# AM32_ESC.net
KiCad netlist of a schematic drawn in Altium Designer
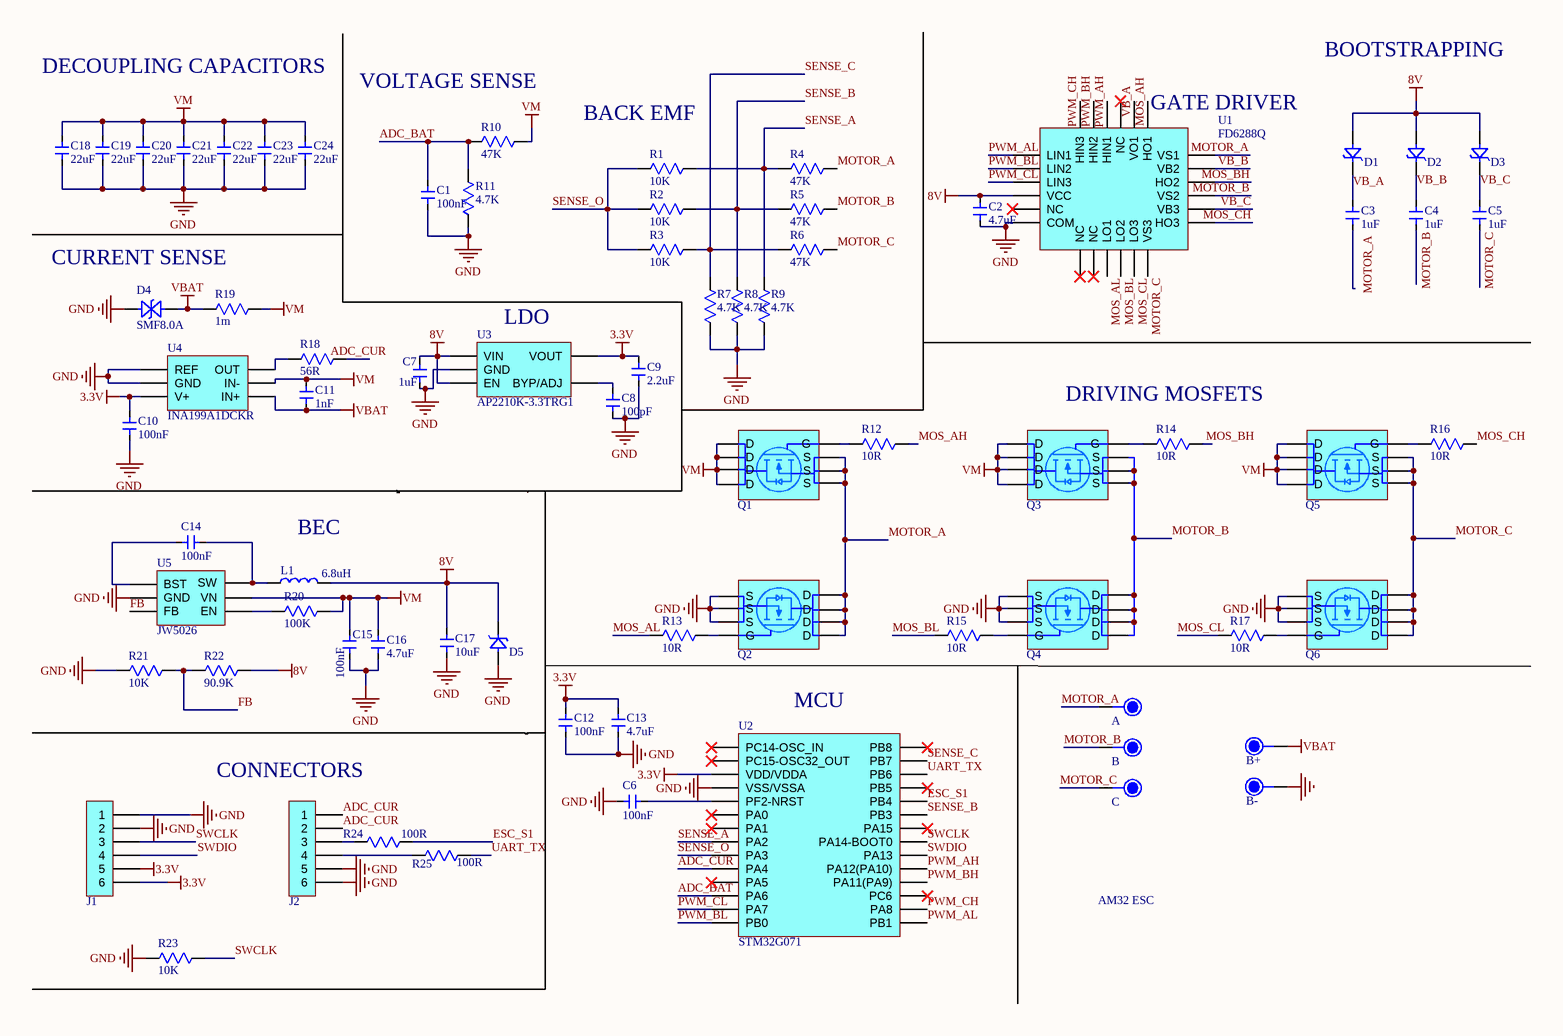
[diagram p0: AM32_ESC.SchDoc]

(export (version "E")
  (design (tool "Eeschema 10.0.6"))
  (components
    (comp (ref "A") (value "PAD") (footprint "PAD") (libsource (lib "AM32_ESC") (part "PAD")))
    (comp (ref "B") (value "PAD") (footprint "PAD") (libsource (lib "AM32_ESC") (part "PAD")))
    (comp (ref "B+") (value "PAD") (footprint "PAD") (libsource (lib "AM32_ESC") (part "PAD")))
    (comp (ref "B-") (value "PAD") (footprint "PAD") (libsource (lib "AM32_ESC") (part "PAD")))
    (comp (ref "C") (value "PAD") (footprint "PAD") (libsource (lib "AM32_ESC") (part "PAD")))
    (comp (ref "C1") (value "100nF") (footprint "C0805") (libsource (lib "AM32_ESC") (part "C100nF")))
    (comp (ref "C2") (value "4.7uF") (footprint "C0603") (libsource (lib "AM32_ESC") (part "C4.7uF")))
    (comp (ref "C3") (value "1uF") (footprint "C0603") (libsource (lib "AM32_ESC") (part "C1uF")))
    (comp (ref "C4") (value "1uF") (footprint "C0603") (libsource (lib "AM32_ESC") (part "C1uF")))
    (comp (ref "C5") (value "1uF") (footprint "C0603") (libsource (lib "AM32_ESC") (part "C1uF")))
    (comp (ref "C6") (value "100nF") (footprint "C0805") (libsource (lib "AM32_ESC") (part "C100nF")))
    (comp (ref "C7") (value "1uF") (footprint "C0603") (libsource (lib "AM32_ESC") (part "C1uF")))
    (comp (ref "C8") (value "100pF") (footprint "C0603") (libsource (lib "AM32_ESC") (part "C100pF")))
    (comp (ref "C9") (value "2.2uF") (footprint "C0603") (libsource (lib "AM32_ESC") (part "C2.2uF")))
    (comp (ref "C10") (value "100nF") (footprint "C0805") (libsource (lib "AM32_ESC") (part "C100nF")))
    (comp (ref "C11") (value "1nF") (footprint "C0603") (libsource (lib "AM32_ESC") (part "C1nF")))
    (comp (ref "C12") (value "100nF") (footprint "C0805") (libsource (lib "AM32_ESC") (part "C100nF")))
    (comp (ref "C13") (value "4.7uF") (footprint "C0603") (libsource (lib "AM32_ESC") (part "C4.7uF")))
    (comp (ref "C14") (value "100nF") (footprint "C0805") (libsource (lib "AM32_ESC") (part "C100nF")))
    (comp (ref "C15") (value "100nF") (footprint "C0805") (libsource (lib "AM32_ESC") (part "C100nF")))
    (comp (ref "C16") (value "4.7uF") (footprint "C0603") (libsource (lib "AM32_ESC") (part "C4.7uF")))
    (comp (ref "C17") (value "10uF") (footprint "C0603") (libsource (lib "AM32_ESC") (part "C10uF")))
    (comp (ref "C18") (value "22uF") (footprint "C0805") (libsource (lib "AM32_ESC") (part "C22uF")))
    (comp (ref "C19") (value "22uF") (footprint "C0805") (libsource (lib "AM32_ESC") (part "C22uF")))
    (comp (ref "C20") (value "22uF") (footprint "C0805") (libsource (lib "AM32_ESC") (part "C22uF")))
    (comp (ref "C21") (value "22uF") (footprint "C0805") (libsource (lib "AM32_ESC") (part "C22uF")))
    (comp (ref "C22") (value "22uF") (footprint "C0805") (libsource (lib "AM32_ESC") (part "C22uF")))
    (comp (ref "C23") (value "22uF") (footprint "C0805") (libsource (lib "AM32_ESC") (part "C22uF")))
    (comp (ref "C24") (value "22uF") (footprint "C0805") (libsource (lib "AM32_ESC") (part "C22uF")))
    (comp (ref "D1") (value "Diode") (footprint "SOD2512X116N") (libsource (lib "AM32_ESC") (part "Diode")))
    (comp (ref "D2") (value "Diode") (footprint "SOD2512X116N") (libsource (lib "AM32_ESC") (part "Diode")))
    (comp (ref "D3") (value "Diode") (footprint "SOD2512X116N") (libsource (lib "AM32_ESC") (part "Diode")))
    (comp (ref "D4") (value "SMF8.0A") (footprint "SMF8.0") (libsource (lib "AM32_ESC") (part "SMF8.0A")))
    (comp (ref "D5") (value "Diode") (footprint "SOD2512X116N") (libsource (lib "AM32_ESC") (part "Diode")))
    (comp (ref "J1") (value "JST_XH") (footprint "6 pin header") (libsource (lib "AM32_ESC") (part "JST_XH")))
    (comp (ref "J2") (value "JST_XH") (footprint "6 pin header") (libsource (lib "AM32_ESC") (part "JST_XH")))
    (comp (ref "L1") (value "6.8uH") (footprint "L0806") (libsource (lib "AM32_ESC") (part "L6.8uH")))
    (comp (ref "Q1")
      (value "CSD19531")
      (footprint "MOSFET_CSD19531Q5A")
      (libsource (lib "") (part "MOSFET_1"))
    )
    (comp (ref "Q2")
      (value "CSD19531")
      (footprint "MOSFET_CSD19531Q5A")
      (libsource (lib "AM32_ESC") (part "MOSFET"))
    )
    (comp (ref "Q3")
      (value "CSD19531")
      (footprint "MOSFET_CSD19531Q5A")
      (libsource (lib "") (part "MOSFET_1"))
    )
    (comp (ref "Q4")
      (value "CSD19531")
      (footprint "MOSFET_CSD19531Q5A")
      (libsource (lib "AM32_ESC") (part "MOSFET"))
    )
    (comp (ref "Q5")
      (value "CSD19531")
      (footprint "MOSFET_CSD19531Q5A")
      (libsource (lib "") (part "MOSFET_1"))
    )
    (comp (ref "Q6")
      (value "CSD19531")
      (footprint "MOSFET_CSD19531Q5A")
      (libsource (lib "AM32_ESC") (part "MOSFET"))
    )
    (comp (ref "R1") (value "10K") (footprint "R0603n") (libsource (lib "AM32_ESC") (part "R10K")))
    (comp (ref "R2") (value "10K") (footprint "R0603n") (libsource (lib "AM32_ESC") (part "R10K")))
    (comp (ref "R3") (value "10K") (footprint "R0603n") (libsource (lib "AM32_ESC") (part "R10K")))
    (comp (ref "R4") (value "47K") (footprint "R0603N") (libsource (lib "AM32_ESC") (part "R47K")))
    (comp (ref "R5") (value "47K") (footprint "R0603N") (libsource (lib "AM32_ESC") (part "R47K")))
    (comp (ref "R6") (value "47K") (footprint "R0603N") (libsource (lib "AM32_ESC") (part "R47K")))
    (comp (ref "R7") (value "4.7K") (footprint "R0603N") (libsource (lib "AM32_ESC") (part "R4.7K")))
    (comp (ref "R8") (value "4.7K") (footprint "R0603N") (libsource (lib "AM32_ESC") (part "R4.7K")))
    (comp (ref "R9") (value "4.7K") (footprint "R0603N") (libsource (lib "AM32_ESC") (part "R4.7K")))
    (comp (ref "R10") (value "47K") (footprint "R0603N") (libsource (lib "AM32_ESC") (part "R47K")))
    (comp (ref "R11") (value "4.7K") (footprint "R0603N") (libsource (lib "AM32_ESC") (part "R4.7K")))
    (comp (ref "R12") (value "10R") (footprint "R0603n") (libsource (lib "AM32_ESC") (part "R10")))
    (comp (ref "R13") (value "10R") (footprint "R0603n") (libsource (lib "AM32_ESC") (part "R10")))
    (comp (ref "R14") (value "10R") (footprint "R0603n") (libsource (lib "AM32_ESC") (part "R10")))
    (comp (ref "R15") (value "10R") (footprint "R0603n") (libsource (lib "AM32_ESC") (part "R10")))
    (comp (ref "R16") (value "10R") (footprint "R0603n") (libsource (lib "AM32_ESC") (part "R10")))
    (comp (ref "R17") (value "10R") (footprint "R0603n") (libsource (lib "AM32_ESC") (part "R10")))
    (comp (ref "R18") (value "56R") (footprint "R0603N") (libsource (lib "AM32_ESC") (part "R56")))
    (comp (ref "R19") (value "1m") (footprint "RESC5025X120N") (libsource (lib "AM32_ESC") (part "R1m")))
    (comp (ref "R20") (value "100K") (footprint "R0603N") (libsource (lib "AM32_ESC") (part "R100K")))
    (comp (ref "R21") (value "10K") (footprint "R0603n") (libsource (lib "AM32_ESC") (part "R10K")))
    (comp (ref "R22") (value "90.9K") (footprint "R0603N") (libsource (lib "AM32_ESC") (part "R90.9k")))
    (comp (ref "R23") (value "10K") (footprint "R0603n") (libsource (lib "AM32_ESC") (part "R10K")))
    (comp (ref "R24") (value "100R") (footprint "R0603") (libsource (lib "AM32_ESC") (part "100R")))
    (comp (ref "R25") (value "100R") (footprint "R0603") (libsource (lib "AM32_ESC") (part "100R")))
    (comp (ref "U1") (value "FD6288Q") (footprint "FD6288Q") (libsource (lib "AM32_ESC") (part "FD6288Q")))
    (comp (ref "U2")
      (value "STM32G071")
      (footprint "STM32G071")
      (libsource (lib "AM32_ESC") (part "STM32G071"))
    )
    (comp (ref "U3")
      (value "AP2210K-3.3TRG1")
      (footprint "AP2210K-3.3TRG1")
      (libsource (lib "AM32_ESC") (part "AP2210K-3.3TRG1"))
    )
    (comp (ref "U4")
      (value "INA199A1DCKR")
      (footprint "INA199A1DCKR")
      (libsource (lib "AM32_ESC") (part "INA199A1DCKR"))
    )
    (comp (ref "U5") (value "JW5026") (footprint "JW5026") (libsource (lib "AM32_ESC") (part "JW5026")))
  )
  (nets
    (net (code "1") (name "/ADC_BAT") (class "Default")
      (node (ref "C1") (pin "2") (pinfunction "2_2") (pintype "passive"))
      (node (ref "R10") (pin "1") (pinfunction "1_1") (pintype "passive"))
      (node (ref "R11") (pin "2") (pinfunction "2_2") (pintype "passive"))
      (node (ref "U2") (pin "12") (pinfunction "PA6_12") (pintype "passive"))
    )
    (net (code "2") (name "/ADC_CUR") (class "Default")
      (node (ref "J2") (pin "1") (pinfunction "1_1") (pintype "passive"))
      (node (ref "J2") (pin "2") (pinfunction "2_2") (pintype "passive"))
      (node (ref "R18") (pin "2") (pinfunction "2_2") (pintype "passive"))
      (node (ref "U2") (pin "10") (pinfunction "PA4_10") (pintype "passive"))
    )
    (net (code "3") (name "/ESC_S1") (class "Default")
      (node (ref "R24") (pin "2") (pinfunction "2_2") (pintype "passive"))
      (node (ref "U2") (pin "24") (pinfunction "PB4_24") (pintype "passive"))
    )
    (net (code "4") (name "/FB") (class "Default")
      (node (ref "R21") (pin "2") (pinfunction "2_2") (pintype "passive"))
      (node (ref "R22") (pin "1") (pinfunction "1_1") (pintype "passive"))
      (node (ref "U5") (pin "3") (pinfunction "FB_3") (pintype "passive"))
    )
    (net (code "5") (name "/MOS_AH") (class "Default")
      (node (ref "R12") (pin "2") (pinfunction "2_2") (pintype "passive"))
      (node (ref "U1") (pin "19") (pinfunction "HO1_19") (pintype "passive"))
    )
    (net (code "6") (name "/MOS_AL") (class "Default")
      (node (ref "R13") (pin "1") (pinfunction "1_1") (pintype "passive"))
      (node (ref "U1") (pin "9") (pinfunction "LO1_9") (pintype "passive"))
    )
    (net (code "7") (name "/MOS_BH") (class "Default")
      (node (ref "R14") (pin "2") (pinfunction "2_2") (pintype "passive"))
      (node (ref "U1") (pin "16") (pinfunction "HO2_16") (pintype "passive"))
    )
    (net (code "8") (name "/MOS_BL") (class "Default")
      (node (ref "R15") (pin "1") (pinfunction "1_1") (pintype "passive"))
      (node (ref "U1") (pin "10") (pinfunction "LO2_10") (pintype "passive"))
    )
    (net (code "9") (name "/MOS_CH") (class "Default")
      (node (ref "R16") (pin "2") (pinfunction "2_2") (pintype "passive"))
      (node (ref "U1") (pin "13") (pinfunction "HO3_13") (pintype "passive"))
    )
    (net (code "10") (name "/MOS_CL") (class "Default")
      (node (ref "R17") (pin "1") (pinfunction "1_1") (pintype "passive"))
      (node (ref "U1") (pin "11") (pinfunction "LO3_11") (pintype "passive"))
    )
    (net (code "11") (name "/MOTOR_A") (class "Default")
      (node (ref "A") (pin "1") (pinfunction "1_1") (pintype "passive"))
      (node (ref "Q1") (pin "1") (pinfunction "S_1") (pintype "passive"))
      (node (ref "Q1") (pin "2") (pinfunction "S_2") (pintype "passive"))
      (node (ref "Q1") (pin "3") (pinfunction "S_3") (pintype "passive"))
      (node (ref "Q2") (pin "5") (pinfunction "D_5") (pintype "passive"))
      (node (ref "Q2") (pin "6") (pinfunction "D_6") (pintype "passive"))
      (node (ref "Q2") (pin "7") (pinfunction "D_7") (pintype "passive"))
      (node (ref "Q2") (pin "8") (pinfunction "D_8") (pintype "passive"))
      (node (ref "R4") (pin "2") (pinfunction "2_2") (pintype "passive"))
      (node (ref "U1") (pin "18") (pinfunction "VS1_18") (pintype "passive"))
    )
    (net (code "12") (name "/MOTOR_B") (class "Default")
      (node (ref "B") (pin "1") (pinfunction "1_1") (pintype "passive"))
      (node (ref "Q3") (pin "1") (pinfunction "S_1") (pintype "passive"))
      (node (ref "Q3") (pin "2") (pinfunction "S_2") (pintype "passive"))
      (node (ref "Q3") (pin "3") (pinfunction "S_3") (pintype "passive"))
      (node (ref "Q4") (pin "5") (pinfunction "D_5") (pintype "passive"))
      (node (ref "Q4") (pin "6") (pinfunction "D_6") (pintype "passive"))
      (node (ref "Q4") (pin "7") (pinfunction "D_7") (pintype "passive"))
      (node (ref "Q4") (pin "8") (pinfunction "D_8") (pintype "passive"))
      (node (ref "R5") (pin "2") (pinfunction "2_2") (pintype "passive"))
      (node (ref "U1") (pin "15") (pinfunction "VS2_15") (pintype "passive"))
    )
    (net (code "13") (name "/MOTOR_C") (class "Default")
      (node (ref "C") (pin "1") (pinfunction "1_1") (pintype "passive"))
      (node (ref "Q5") (pin "1") (pinfunction "S_1") (pintype "passive"))
      (node (ref "Q5") (pin "2") (pinfunction "S_2") (pintype "passive"))
      (node (ref "Q5") (pin "3") (pinfunction "S_3") (pintype "passive"))
      (node (ref "Q6") (pin "5") (pinfunction "D_5") (pintype "passive"))
      (node (ref "Q6") (pin "6") (pinfunction "D_6") (pintype "passive"))
      (node (ref "Q6") (pin "7") (pinfunction "D_7") (pintype "passive"))
      (node (ref "Q6") (pin "8") (pinfunction "D_8") (pintype "passive"))
      (node (ref "R6") (pin "2") (pinfunction "2_2") (pintype "passive"))
      (node (ref "U1") (pin "12") (pinfunction "VS3_12") (pintype "passive"))
    )
    (net (code "14") (name "/PWM_AH") (class "Default")
      (node (ref "U1") (pin "22") (pinfunction "HIN1_22") (pintype "passive"))
      (node (ref "U2") (pin "19") (pinfunction "PA12(PA10)_19") (pintype "passive"))
    )
    (net (code "15") (name "/PWM_AL") (class "Default")
      (node (ref "U1") (pin "1") (pinfunction "LIN1_1") (pintype "passive"))
      (node (ref "U2") (pin "15") (pinfunction "PB1_15") (pintype "passive"))
    )
    (net (code "16") (name "/PWM_BH") (class "Default")
      (node (ref "U1") (pin "23") (pinfunction "HIN2_23") (pintype "passive"))
      (node (ref "U2") (pin "18") (pinfunction "PA11(PA9)_18") (pintype "passive"))
    )
    (net (code "17") (name "/PWM_BL") (class "Default")
      (node (ref "U1") (pin "2") (pinfunction "LIN2_2") (pintype "passive"))
      (node (ref "U2") (pin "14") (pinfunction "PB0_14") (pintype "passive"))
    )
    (net (code "18") (name "/PWM_CH") (class "Default")
      (node (ref "U1") (pin "24") (pinfunction "HIN3_24") (pintype "passive"))
      (node (ref "U2") (pin "16") (pinfunction "PA8_16") (pintype "passive"))
    )
    (net (code "19") (name "/PWM_CL") (class "Default")
      (node (ref "U1") (pin "3") (pinfunction "LIN3_3") (pintype "passive"))
      (node (ref "U2") (pin "13") (pinfunction "PA7_13") (pintype "passive"))
    )
    (net (code "20") (name "/SENSE_A") (class "Default")
      (node (ref "R1") (pin "2") (pinfunction "2_2") (pintype "passive"))
      (node (ref "R4") (pin "1") (pinfunction "1_1") (pintype "passive"))
      (node (ref "R9") (pin "2") (pinfunction "2_2") (pintype "passive"))
      (node (ref "U2") (pin "8") (pinfunction "PA2_8") (pintype "passive"))
    )
    (net (code "21") (name "/SENSE_B") (class "Default")
      (node (ref "R2") (pin "2") (pinfunction "2_2") (pintype "passive"))
      (node (ref "R5") (pin "1") (pinfunction "1_1") (pintype "passive"))
      (node (ref "R8") (pin "2") (pinfunction "2_2") (pintype "passive"))
      (node (ref "U2") (pin "23") (pinfunction "PB3_23") (pintype "passive"))
    )
    (net (code "22") (name "/SENSE_C") (class "Default")
      (node (ref "R3") (pin "2") (pinfunction "2_2") (pintype "passive"))
      (node (ref "R6") (pin "1") (pinfunction "1_1") (pintype "passive"))
      (node (ref "R7") (pin "2") (pinfunction "2_2") (pintype "passive"))
      (node (ref "U2") (pin "27") (pinfunction "PB7_27") (pintype "passive"))
    )
    (net (code "23") (name "/SENSE_O") (class "Default")
      (node (ref "R1") (pin "1") (pinfunction "1_1") (pintype "passive"))
      (node (ref "R2") (pin "1") (pinfunction "1_1") (pintype "passive"))
      (node (ref "R3") (pin "1") (pinfunction "1_1") (pintype "passive"))
      (node (ref "U2") (pin "9") (pinfunction "PA3_9") (pintype "passive"))
    )
    (net (code "24") (name "/SWCLK") (class "Default")
      (node (ref "J1") (pin "3") (pinfunction "3_3") (pintype "passive"))
      (node (ref "R23") (pin "1") (pinfunction "1_1") (pintype "passive"))
      (node (ref "U2") (pin "21") (pinfunction "PA14-BOOT0_21") (pintype "passive"))
    )
    (net (code "25") (name "/SWDIO") (class "Default")
      (node (ref "J1") (pin "4") (pinfunction "4_4") (pintype "passive"))
      (node (ref "U2") (pin "20") (pinfunction "PA13_20") (pintype "passive"))
    )
    (net (code "26") (name "/UART_TX") (class "Default")
      (node (ref "R25") (pin "2") (pinfunction "2_2") (pintype "passive"))
      (node (ref "U2") (pin "26") (pinfunction "PB6_26") (pintype "passive"))
    )
    (net (code "27") (name "/VB_A") (class "Default")
      (node (ref "C3") (pin "2") (pinfunction "2_2") (pintype "passive"))
      (node (ref "D1") (pin "2") (pinfunction "2_2") (pintype "passive"))
      (node (ref "U1") (pin "20") (pinfunction "VO1_20") (pintype "passive"))
    )
    (net (code "28") (name "/VB_B") (class "Default")
      (node (ref "C4") (pin "2") (pinfunction "2_2") (pintype "passive"))
      (node (ref "D2") (pin "2") (pinfunction "2_2") (pintype "passive"))
      (node (ref "U1") (pin "17") (pinfunction "VB2_17") (pintype "passive"))
    )
    (net (code "29") (name "/VB_C") (class "Default")
      (node (ref "C5") (pin "2") (pinfunction "2_2") (pintype "passive"))
      (node (ref "D3") (pin "2") (pinfunction "2_2") (pintype "passive"))
      (node (ref "U1") (pin "14") (pinfunction "VB3_14") (pintype "passive"))
    )
    (net (code "30") (name "3.3V") (class "Default")
      (node (ref "C10") (pin "2") (pinfunction "2_2") (pintype "passive"))
      (node (ref "C12") (pin "2") (pinfunction "2_2") (pintype "passive"))
      (node (ref "C13") (pin "2") (pinfunction "2_2") (pintype "passive"))
      (node (ref "C9") (pin "1") (pinfunction "1_1") (pintype "passive"))
      (node (ref "J1") (pin "5") (pinfunction "5_5") (pintype "passive"))
      (node (ref "J1") (pin "6") (pinfunction "6_6") (pintype "passive"))
      (node (ref "U2") (pin "3") (pinfunction "VDD/VDDA_3") (pintype "passive"))
      (node (ref "U3") (pin "5") (pinfunction "VOUT_5") (pintype "passive"))
      (node (ref "U4") (pin "3") (pinfunction "V+_3") (pintype "passive"))
    )
    (net (code "31") (name "8V") (class "Default")
      (node (ref "C17") (pin "2") (pinfunction "2_2") (pintype "passive"))
      (node (ref "C2") (pin "2") (pinfunction "2_2") (pintype "passive"))
      (node (ref "C7") (pin "2") (pinfunction "2_2") (pintype "passive"))
      (node (ref "D1") (pin "1") (pinfunction "1_1") (pintype "passive"))
      (node (ref "D2") (pin "1") (pinfunction "1_1") (pintype "passive"))
      (node (ref "D3") (pin "1") (pinfunction "1_1") (pintype "passive"))
      (node (ref "D5") (pin "2") (pinfunction "2_2") (pintype "passive"))
      (node (ref "L1") (pin "2") (pinfunction "2_2") (pintype "passive"))
      (node (ref "R22") (pin "2") (pinfunction "2_2") (pintype "passive"))
      (node (ref "U1") (pin "4") (pinfunction "VCC_4") (pintype "passive"))
      (node (ref "U3") (pin "1") (pinfunction "VIN_1") (pintype "passive"))
      (node (ref "U3") (pin "3") (pinfunction "EN_3") (pintype "passive"))
    )
    (net (code "32") (name "GND") (class "Default")
      (node (ref "B-") (pin "1") (pinfunction "1_1") (pintype "passive"))
      (node (ref "C1") (pin "1") (pinfunction "1_1") (pintype "passive"))
      (node (ref "C10") (pin "1") (pinfunction "1_1") (pintype "passive"))
      (node (ref "C12") (pin "1") (pinfunction "1_1") (pintype "passive"))
      (node (ref "C13") (pin "1") (pinfunction "1_1") (pintype "passive"))
      (node (ref "C15") (pin "1") (pinfunction "1_1") (pintype "passive"))
      (node (ref "C16") (pin "1") (pinfunction "1_1") (pintype "passive"))
      (node (ref "C17") (pin "1") (pinfunction "1_1") (pintype "passive"))
      (node (ref "C18") (pin "1") (pinfunction "1_1") (pintype "passive"))
      (node (ref "C19") (pin "1") (pinfunction "1_1") (pintype "passive"))
      (node (ref "C2") (pin "1") (pinfunction "1_1") (pintype "passive"))
      (node (ref "C20") (pin "1") (pinfunction "1_1") (pintype "passive"))
      (node (ref "C21") (pin "1") (pinfunction "1_1") (pintype "passive"))
      (node (ref "C22") (pin "1") (pinfunction "1_1") (pintype "passive"))
      (node (ref "C23") (pin "1") (pinfunction "1_1") (pintype "passive"))
      (node (ref "C24") (pin "1") (pinfunction "1_1") (pintype "passive"))
      (node (ref "C6") (pin "1") (pinfunction "1_1") (pintype "passive"))
      (node (ref "C7") (pin "1") (pinfunction "1_1") (pintype "passive"))
      (node (ref "C8") (pin "2") (pinfunction "2_2") (pintype "passive"))
      (node (ref "C9") (pin "2") (pinfunction "2_2") (pintype "passive"))
      (node (ref "D4") (pin "1") (pinfunction "1_1") (pintype "passive"))
      (node (ref "D5") (pin "1") (pinfunction "1_1") (pintype "passive"))
      (node (ref "J1") (pin "1") (pinfunction "1_1") (pintype "passive"))
      (node (ref "J1") (pin "2") (pinfunction "2_2") (pintype "passive"))
      (node (ref "J2") (pin "5") (pinfunction "5_5") (pintype "passive"))
      (node (ref "J2") (pin "6") (pinfunction "6_6") (pintype "passive"))
      (node (ref "Q2") (pin "1") (pinfunction "S_1") (pintype "passive"))
      (node (ref "Q2") (pin "2") (pinfunction "S_2") (pintype "passive"))
      (node (ref "Q2") (pin "3") (pinfunction "S_3") (pintype "passive"))
      (node (ref "Q4") (pin "1") (pinfunction "S_1") (pintype "passive"))
      (node (ref "Q4") (pin "2") (pinfunction "S_2") (pintype "passive"))
      (node (ref "Q4") (pin "3") (pinfunction "S_3") (pintype "passive"))
      (node (ref "Q6") (pin "1") (pinfunction "S_1") (pintype "passive"))
      (node (ref "Q6") (pin "2") (pinfunction "S_2") (pintype "passive"))
      (node (ref "Q6") (pin "3") (pinfunction "S_3") (pintype "passive"))
      (node (ref "R11") (pin "1") (pinfunction "1_1") (pintype "passive"))
      (node (ref "R21") (pin "1") (pinfunction "1_1") (pintype "passive"))
      (node (ref "R23") (pin "2") (pinfunction "2_2") (pintype "passive"))
      (node (ref "R7") (pin "1") (pinfunction "1_1") (pintype "passive"))
      (node (ref "R8") (pin "1") (pinfunction "1_1") (pintype "passive"))
      (node (ref "R9") (pin "1") (pinfunction "1_1") (pintype "passive"))
      (node (ref "U1") (pin "6") (pinfunction "COM_6") (pintype "passive"))
      (node (ref "U2") (pin "4") (pinfunction "VSS/VSSA_4") (pintype "passive"))
      (node (ref "U3") (pin "2") (pinfunction "GND_2") (pintype "passive"))
      (node (ref "U4") (pin "1") (pinfunction "REF_1") (pintype "passive"))
      (node (ref "U4") (pin "2") (pinfunction "GND_2") (pintype "passive"))
      (node (ref "U5") (pin "2") (pinfunction "GND_2") (pintype "passive"))
    )
    (net (code "33") (name "Net-(J2-Pad3)") (class "Default")
      (node (ref "J2") (pin "3") (pinfunction "3_3") (pintype "passive"))
      (node (ref "R24") (pin "1") (pinfunction "1_1") (pintype "passive"))
    )
    (net (code "34") (name "Net-(J2-Pad4)") (class "Default")
      (node (ref "J2") (pin "4") (pinfunction "4_4") (pintype "passive"))
      (node (ref "R25") (pin "1") (pinfunction "1_1") (pintype "passive"))
    )
    (net (code "35") (name "Net-(Q1-G)") (class "Default")
      (node (ref "Q1") (pin "4") (pinfunction "G_4") (pintype "passive"))
      (node (ref "R12") (pin "1") (pinfunction "1_1") (pintype "passive"))
    )
    (net (code "36") (name "Net-(Q2-G)") (class "Default")
      (node (ref "Q2") (pin "4") (pinfunction "G_4") (pintype "passive"))
      (node (ref "R13") (pin "2") (pinfunction "2_2") (pintype "passive"))
    )
    (net (code "37") (name "Net-(Q3-G)") (class "Default")
      (node (ref "Q3") (pin "4") (pinfunction "G_4") (pintype "passive"))
      (node (ref "R14") (pin "1") (pinfunction "1_1") (pintype "passive"))
    )
    (net (code "38") (name "Net-(Q4-G)") (class "Default")
      (node (ref "Q4") (pin "4") (pinfunction "G_4") (pintype "passive"))
      (node (ref "R15") (pin "2") (pinfunction "2_2") (pintype "passive"))
    )
    (net (code "39") (name "Net-(Q5-G)") (class "Default")
      (node (ref "Q5") (pin "4") (pinfunction "G_4") (pintype "passive"))
      (node (ref "R16") (pin "1") (pinfunction "1_1") (pintype "passive"))
    )
    (net (code "40") (name "Net-(Q6-G)") (class "Default")
      (node (ref "Q6") (pin "4") (pinfunction "G_4") (pintype "passive"))
      (node (ref "R17") (pin "2") (pinfunction "2_2") (pintype "passive"))
    )
    (net (code "41") (name "Net-(U2-PF2-NRST)") (class "Default")
      (node (ref "C6") (pin "2") (pinfunction "2_2") (pintype "passive"))
      (node (ref "U2") (pin "5") (pinfunction "PF2-NRST_5") (pintype "passive"))
    )
    (net (code "42") (name "Net-(U3-BYP{slash}ADJ)") (class "Default")
      (node (ref "C8") (pin "1") (pinfunction "1_1") (pintype "passive"))
      (node (ref "U3") (pin "4") (pinfunction "BYP/ADJ_4") (pintype "passive"))
    )
    (net (code "43") (name "Net-(U4-OUT)") (class "Default")
      (node (ref "R18") (pin "1") (pinfunction "1_1") (pintype "passive"))
      (node (ref "U4") (pin "6") (pinfunction "OUT_6") (pintype "passive"))
    )
    (net (code "44") (name "Net-(U5-BST)") (class "Default")
      (node (ref "C14") (pin "1") (pinfunction "1_1") (pintype "passive"))
      (node (ref "U5") (pin "1") (pinfunction "BST_1") (pintype "passive"))
    )
    (net (code "45") (name "Net-(U5-EN)") (class "Default")
      (node (ref "R20") (pin "1") (pinfunction "1_1") (pintype "passive"))
      (node (ref "U5") (pin "4") (pinfunction "EN_4") (pintype "passive"))
    )
    (net (code "46") (name "Net-(U5-SW)") (class "Default")
      (node (ref "C14") (pin "2") (pinfunction "2_2") (pintype "passive"))
      (node (ref "L1") (pin "1") (pinfunction "1_1") (pintype "passive"))
      (node (ref "U5") (pin "6") (pinfunction "SW_6") (pintype "passive"))
    )
    (net (code "47") (name "VBAT") (class "Default")
      (node (ref "B+") (pin "1") (pinfunction "1_1") (pintype "passive"))
      (node (ref "C11") (pin "1") (pinfunction "1_1") (pintype "passive"))
      (node (ref "D4") (pin "2") (pinfunction "2_2") (pintype "passive"))
      (node (ref "R19") (pin "1") (pinfunction "1_1") (pintype "passive"))
      (node (ref "U4") (pin "4") (pinfunction "IN+_4") (pintype "passive"))
    )
    (net (code "48") (name "VM") (class "Default")
      (node (ref "C11") (pin "2") (pinfunction "2_2") (pintype "passive"))
      (node (ref "C15") (pin "2") (pinfunction "2_2") (pintype "passive"))
      (node (ref "C16") (pin "2") (pinfunction "2_2") (pintype "passive"))
      (node (ref "C18") (pin "2") (pinfunction "2_2") (pintype "passive"))
      (node (ref "C19") (pin "2") (pinfunction "2_2") (pintype "passive"))
      (node (ref "C20") (pin "2") (pinfunction "2_2") (pintype "passive"))
      (node (ref "C21") (pin "2") (pinfunction "2_2") (pintype "passive"))
      (node (ref "C22") (pin "2") (pinfunction "2_2") (pintype "passive"))
      (node (ref "C23") (pin "2") (pinfunction "2_2") (pintype "passive"))
      (node (ref "C24") (pin "2") (pinfunction "2_2") (pintype "passive"))
      (node (ref "Q1") (pin "5") (pinfunction "D_5") (pintype "passive"))
      (node (ref "Q1") (pin "6") (pinfunction "D_6") (pintype "passive"))
      (node (ref "Q1") (pin "7") (pinfunction "D_7") (pintype "passive"))
      (node (ref "Q1") (pin "8") (pinfunction "D_8") (pintype "passive"))
      (node (ref "Q3") (pin "5") (pinfunction "D_5") (pintype "passive"))
      (node (ref "Q3") (pin "6") (pinfunction "D_6") (pintype "passive"))
      (node (ref "Q3") (pin "7") (pinfunction "D_7") (pintype "passive"))
      (node (ref "Q3") (pin "8") (pinfunction "D_8") (pintype "passive"))
      (node (ref "Q5") (pin "5") (pinfunction "D_5") (pintype "passive"))
      (node (ref "Q5") (pin "6") (pinfunction "D_6") (pintype "passive"))
      (node (ref "Q5") (pin "7") (pinfunction "D_7") (pintype "passive"))
      (node (ref "Q5") (pin "8") (pinfunction "D_8") (pintype "passive"))
      (node (ref "R10") (pin "2") (pinfunction "2_2") (pintype "passive"))
      (node (ref "R19") (pin "2") (pinfunction "2_2") (pintype "passive"))
      (node (ref "R20") (pin "2") (pinfunction "2_2") (pintype "passive"))
      (node (ref "U4") (pin "5") (pinfunction "IN-_5") (pintype "passive"))
      (node (ref "U5") (pin "5") (pinfunction "VN_5") (pintype "passive"))
    )
    (net (code "49") (name "unconnected-(C3-Pad1)") (class "Default")
      (node (ref "C3") (pin "1") (pinfunction "1_1") (pintype "passive"))
    )
    (net (code "50") (name "unconnected-(C4-Pad1)") (class "Default")
      (node (ref "C4") (pin "1") (pinfunction "1_1") (pintype "passive"))
    )
    (net (code "51") (name "unconnected-(C5-Pad1)") (class "Default")
      (node (ref "C5") (pin "1") (pinfunction "1_1") (pintype "passive"))
    )
    (net (code "52") (name "unconnected-(U1-NC-Pad5)") (class "Default")
      (node (ref "U1") (pin "5") (pinfunction "NC_5") (pintype "passive+no_connect"))
    )
    (net (code "53") (name "unconnected-(U1-NC-Pad7)") (class "Default")
      (node (ref "U1") (pin "7") (pinfunction "NC_7") (pintype "passive+no_connect"))
    )
    (net (code "54") (name "unconnected-(U1-NC-Pad8)") (class "Default")
      (node (ref "U1") (pin "8") (pinfunction "NC_8") (pintype "passive+no_connect"))
    )
    (net (code "55") (name "unconnected-(U1-NC-Pad21)") (class "Default")
      (node (ref "U1") (pin "21") (pinfunction "NC_21") (pintype "passive+no_connect"))
    )
    (net (code "56") (name "unconnected-(U2-PA0-Pad6)") (class "Default")
      (node (ref "U2") (pin "6") (pinfunction "PA0_6") (pintype "passive+no_connect"))
    )
    (net (code "57") (name "unconnected-(U2-PA1-Pad7)") (class "Default")
      (node (ref "U2") (pin "7") (pinfunction "PA1_7") (pintype "passive+no_connect"))
    )
    (net (code "58") (name "unconnected-(U2-PA5-Pad11)") (class "Default")
      (node (ref "U2") (pin "11") (pinfunction "PA5_11") (pintype "passive+no_connect"))
    )
    (net (code "59") (name "unconnected-(U2-PA15-Pad22)") (class "Default")
      (node (ref "U2") (pin "22") (pinfunction "PA15_22") (pintype "passive+no_connect"))
    )
    (net (code "60") (name "unconnected-(U2-PB5-Pad25)") (class "Default")
      (node (ref "U2") (pin "25") (pinfunction "PB5_25") (pintype "passive+no_connect"))
    )
    (net (code "61") (name "unconnected-(U2-PB8-Pad28)") (class "Default")
      (node (ref "U2") (pin "28") (pinfunction "PB8_28") (pintype "passive+no_connect"))
    )
    (net (code "62") (name "unconnected-(U2-PC6-Pad17)") (class "Default")
      (node (ref "U2") (pin "17") (pinfunction "PC6_17") (pintype "passive+no_connect"))
    )
    (net (code "63") (name "unconnected-(U2-PC14-OSC_IN-Pad1)") (class "Default")
      (node (ref "U2") (pin "1") (pinfunction "PC14-OSC_IN_1") (pintype "passive+no_connect"))
    )
    (net (code "64") (name "unconnected-(U2-PC15-OSC32_OUT-Pad2)") (class "Default")
      (node (ref "U2") (pin "2") (pinfunction "PC15-OSC32_OUT_2") (pintype "passive+no_connect"))
    )
  )
)
